# reverb.net
KiCad netlist of a schematic drawn in EAGLE
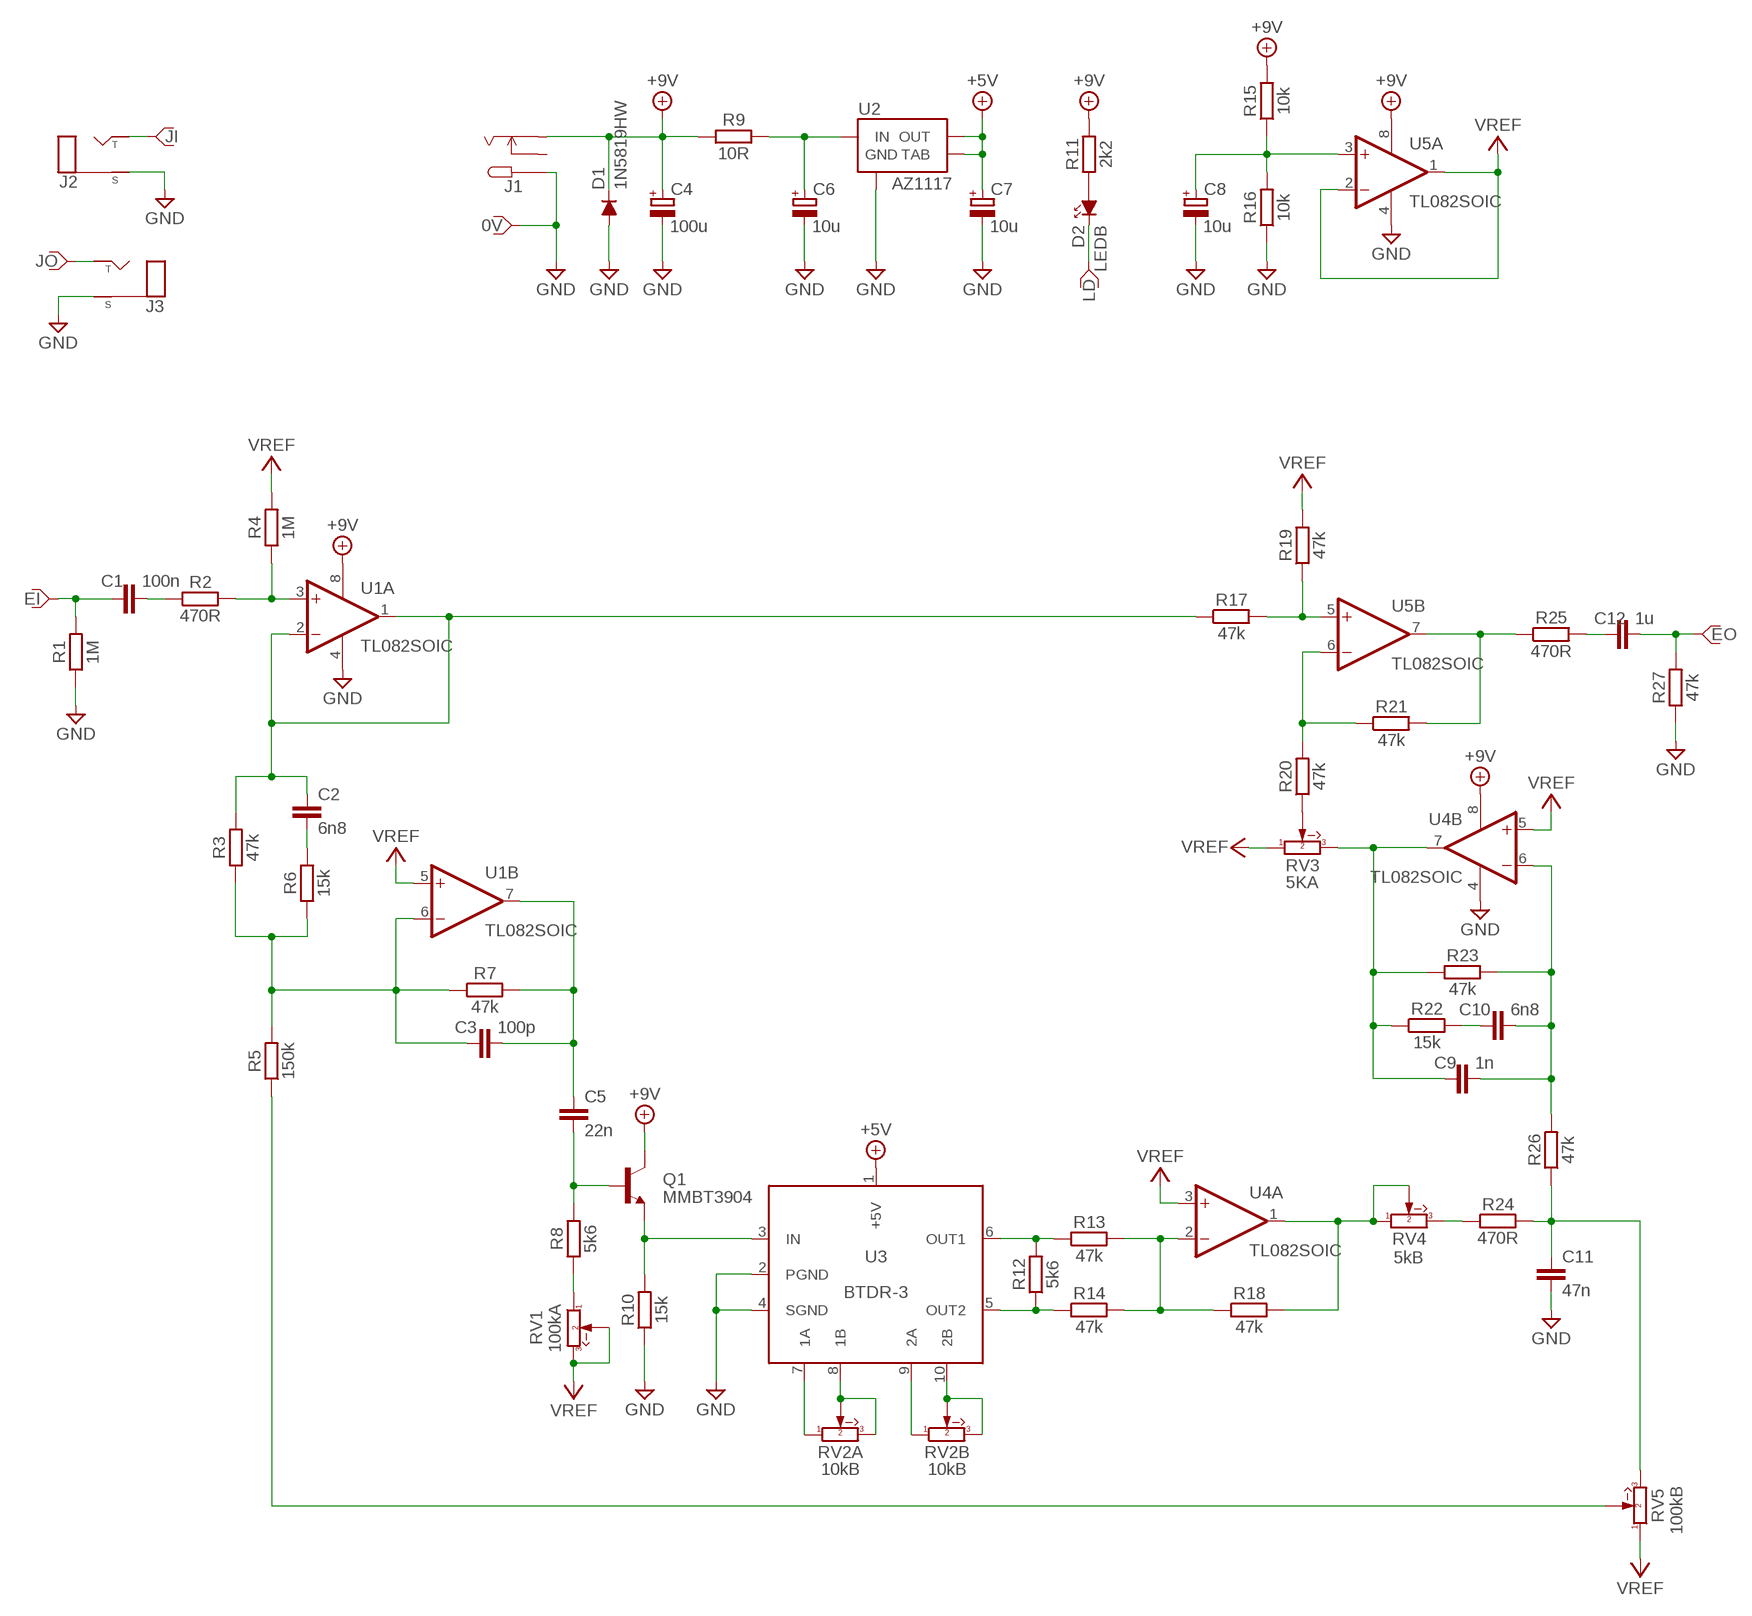
[diagram p0: schematic, sheet 1]

(export (version "E")
  (design (tool "Eeschema 10.0.6"))
  (components
    (comp (ref "C1")
      (value "100n")
      (footprint "eagle-import:C_0603")
      (libsource (lib "eagle-import") (part "CAPACITOR0603"))
    )
    (comp (ref "C2")
      (value "6n8")
      (footprint "eagle-import:C_0603")
      (libsource (lib "eagle-import") (part "CAPACITOR0603"))
    )
    (comp (ref "C3")
      (value "100p")
      (footprint "eagle-import:C_0603")
      (libsource (lib "eagle-import") (part "CAPACITOR0603"))
    )
    (comp (ref "C4")
      (value "100u")
      (footprint "eagle-import:C_E_TH_5MM")
      (libsource (lib "eagle-import") (part "CAPACITOR_POLARISEDTH_5MM"))
    )
    (comp (ref "C5")
      (value "22n")
      (footprint "eagle-import:C_0603")
      (libsource (lib "eagle-import") (part "CAPACITOR0603"))
    )
    (comp (ref "C6")
      (value "10u")
      (footprint "eagle-import:C_E_TH_5MM")
      (libsource (lib "eagle-import") (part "CAPACITOR_POLARISEDTH_5MM"))
    )
    (comp (ref "C7")
      (value "10u")
      (footprint "eagle-import:C_E_TH_5MM")
      (libsource (lib "eagle-import") (part "CAPACITOR_POLARISEDTH_5MM"))
    )
    (comp (ref "C8")
      (value "10u")
      (footprint "eagle-import:C_E_TH_5MM")
      (libsource (lib "eagle-import") (part "CAPACITOR_POLARISEDTH_5MM"))
    )
    (comp (ref "C9")
      (value "1n")
      (footprint "eagle-import:C_0603")
      (libsource (lib "eagle-import") (part "CAPACITOR0603"))
    )
    (comp (ref "C10")
      (value "6n8")
      (footprint "eagle-import:C_0603")
      (libsource (lib "eagle-import") (part "CAPACITOR0603"))
    )
    (comp (ref "C11")
      (value "47n")
      (footprint "eagle-import:C_0603")
      (libsource (lib "eagle-import") (part "CAPACITOR0603"))
    )
    (comp (ref "C12")
      (value "1u")
      (footprint "eagle-import:C_0603")
      (libsource (lib "eagle-import") (part "CAPACITOR0603"))
    )
    (comp (ref "D1")
      (value "1N5819HW")
      (footprint "eagle-import:SOD123")
      (libsource (lib "eagle-import") (part "1N5819HW"))
    )
    (comp (ref "D2")
      (value "LEDB")
      (footprint "eagle-import:LED_5MM")
      (libsource (lib "eagle-import") (part "LEDB"))
    )
    (comp (ref "J1")
      (value "DC_JACK_C2")
      (footprint "eagle-import:DC_JACK_CON_2MM")
      (libsource (lib "eagle-import") (part "DC_JACK_C2"))
    )
    (comp (ref "J2")
      (value "MONOJACK2MM")
      (footprint "eagle-import:MONOJACK_CON_2MM")
      (libsource (lib "eagle-import") (part "MONOJACK2MM"))
    )
    (comp (ref "J3")
      (value "MONOJACK2MM")
      (footprint "eagle-import:MONOJACK_CON_2MM")
      (libsource (lib "eagle-import") (part "MONOJACK2MM"))
    )
    (comp (ref "P1")
      (value "0V")
      (footprint "eagle-import:CON_PIN")
      (libsource (lib "eagle-import") (part "CON_PIN"))
    )
    (comp (ref "P2")
      (value "LD")
      (footprint "eagle-import:CON_PIN")
      (libsource (lib "eagle-import") (part "CON_PIN"))
    )
    (comp (ref "P3")
      (value "JO")
      (footprint "eagle-import:CON_PIN")
      (libsource (lib "eagle-import") (part "CON_PIN"))
    )
    (comp (ref "P4")
      (value "JI")
      (footprint "eagle-import:CON_PIN")
      (libsource (lib "eagle-import") (part "CON_PIN"))
    )
    (comp (ref "P5")
      (value "EO")
      (footprint "eagle-import:CON_PIN")
      (libsource (lib "eagle-import") (part "CON_PIN"))
    )
    (comp (ref "P6")
      (value "EI")
      (footprint "eagle-import:CON_PIN")
      (libsource (lib "eagle-import") (part "CON_PIN"))
    )
    (comp (ref "Q1")
      (value "MMBT3904")
      (footprint "eagle-import:SOT23")
      (libsource (lib "eagle-import") (part "MMBT3904"))
    )
    (comp (ref "R1")
      (value "1M")
      (footprint "eagle-import:R_0603")
      (libsource (lib "eagle-import") (part "RESISTOR0603"))
    )
    (comp (ref "R2")
      (value "470R")
      (footprint "eagle-import:R_0603")
      (libsource (lib "eagle-import") (part "RESISTOR0603"))
    )
    (comp (ref "R3")
      (value "47k")
      (footprint "eagle-import:R_0603")
      (libsource (lib "eagle-import") (part "RESISTOR0603"))
    )
    (comp (ref "R4")
      (value "1M")
      (footprint "eagle-import:R_0603")
      (libsource (lib "eagle-import") (part "RESISTOR0603"))
    )
    (comp (ref "R5")
      (value "150k")
      (footprint "eagle-import:R_0603")
      (libsource (lib "eagle-import") (part "RESISTOR0603"))
    )
    (comp (ref "R6")
      (value "15k")
      (footprint "eagle-import:R_0603")
      (libsource (lib "eagle-import") (part "RESISTOR0603"))
    )
    (comp (ref "R7")
      (value "47k")
      (footprint "eagle-import:R_0603")
      (libsource (lib "eagle-import") (part "RESISTOR0603"))
    )
    (comp (ref "R8")
      (value "5k6")
      (footprint "eagle-import:R_0603")
      (libsource (lib "eagle-import") (part "RESISTOR0603"))
    )
    (comp (ref "R9")
      (value "10R")
      (footprint "eagle-import:R_0603")
      (libsource (lib "eagle-import") (part "RESISTOR0603"))
    )
    (comp (ref "R10")
      (value "15k")
      (footprint "eagle-import:R_0603")
      (libsource (lib "eagle-import") (part "RESISTOR0603"))
    )
    (comp (ref "R11")
      (value "2k2")
      (footprint "eagle-import:R_0603")
      (libsource (lib "eagle-import") (part "RESISTOR0603"))
    )
    (comp (ref "R12")
      (value "5k6")
      (footprint "eagle-import:R_0603")
      (libsource (lib "eagle-import") (part "RESISTOR0603"))
    )
    (comp (ref "R13")
      (value "47k")
      (footprint "eagle-import:R_0603")
      (libsource (lib "eagle-import") (part "RESISTOR0603"))
    )
    (comp (ref "R14")
      (value "47k")
      (footprint "eagle-import:R_0603")
      (libsource (lib "eagle-import") (part "RESISTOR0603"))
    )
    (comp (ref "R15")
      (value "10k")
      (footprint "eagle-import:R_0603")
      (libsource (lib "eagle-import") (part "RESISTOR0603"))
    )
    (comp (ref "R16")
      (value "10k")
      (footprint "eagle-import:R_0603")
      (libsource (lib "eagle-import") (part "RESISTOR0603"))
    )
    (comp (ref "R17")
      (value "47k")
      (footprint "eagle-import:R_0603")
      (libsource (lib "eagle-import") (part "RESISTOR0603"))
    )
    (comp (ref "R18")
      (value "47k")
      (footprint "eagle-import:R_0603")
      (libsource (lib "eagle-import") (part "RESISTOR0603"))
    )
    (comp (ref "R19")
      (value "47k")
      (footprint "eagle-import:R_0603")
      (libsource (lib "eagle-import") (part "RESISTOR0603"))
    )
    (comp (ref "R20")
      (value "47k")
      (footprint "eagle-import:R_0603")
      (libsource (lib "eagle-import") (part "RESISTOR0603"))
    )
    (comp (ref "R21")
      (value "47k")
      (footprint "eagle-import:R_0603")
      (libsource (lib "eagle-import") (part "RESISTOR0603"))
    )
    (comp (ref "R22")
      (value "15k")
      (footprint "eagle-import:R_0603")
      (libsource (lib "eagle-import") (part "RESISTOR0603"))
    )
    (comp (ref "R23")
      (value "47k")
      (footprint "eagle-import:R_0603")
      (libsource (lib "eagle-import") (part "RESISTOR0603"))
    )
    (comp (ref "R24")
      (value "470R")
      (footprint "eagle-import:R_0603")
      (libsource (lib "eagle-import") (part "RESISTOR0603"))
    )
    (comp (ref "R25")
      (value "470R")
      (footprint "eagle-import:R_0603")
      (libsource (lib "eagle-import") (part "RESISTOR0603"))
    )
    (comp (ref "R26")
      (value "47k")
      (footprint "eagle-import:R_0603")
      (libsource (lib "eagle-import") (part "RESISTOR0603"))
    )
    (comp (ref "R27")
      (value "47k")
      (footprint "eagle-import:R_0603")
      (libsource (lib "eagle-import") (part "RESISTOR0603"))
    )
    (comp (ref "RV1")
      (value "100kA")
      (footprint "eagle-import:R_V_ALPHA_PCB_16MM")
      (libsource (lib "eagle-import") (part "POTENTIOMETERA"))
    )
    (comp (ref "RV2")
      (value "10kB")
      (footprint "eagle-import:R_V_ALPHA_PCB_16MM_DUAL")
      (libsource (lib "eagle-import") (part "POTENTIOMETER_DUALA"))
    )
    (comp (ref "RV3")
      (value "5KA")
      (footprint "eagle-import:R_V_ALPHA_PCB_16MM")
      (libsource (lib "eagle-import") (part "POTENTIOMETERA"))
    )
    (comp (ref "RV4")
      (value "5kB")
      (footprint "eagle-import:R_V_ALPHA_PCB_16MM")
      (libsource (lib "eagle-import") (part "POTENTIOMETERA"))
    )
    (comp (ref "RV5")
      (value "100kB")
      (footprint "eagle-import:R_V_ALPHA_PCB_16MM")
      (libsource (lib "eagle-import") (part "POTENTIOMETERA"))
    )
    (comp (ref "U1")
      (value "TL082SOIC")
      (footprint "eagle-import:SOIC8")
      (libsource (lib "eagle-import") (part "TL082SOIC"))
    )
    (comp (ref "U2")
      (value "AZ1117")
      (footprint "eagle-import:SOT223")
      (libsource (lib "eagle-import") (part "AZ1117"))
    )
    (comp (ref "U3")
      (value "BTDR-3")
      (footprint "eagle-import:BTDR-3")
      (libsource (lib "eagle-import") (part "BTDR-3"))
    )
    (comp (ref "U4")
      (value "TL082SOIC")
      (footprint "eagle-import:SOIC8")
      (libsource (lib "eagle-import") (part "TL082SOIC"))
    )
    (comp (ref "U5")
      (value "TL082SOIC")
      (footprint "eagle-import:SOIC8")
      (libsource (lib "eagle-import") (part "TL082SOIC"))
    )
  )
  (nets
    (net (code "1") (name "+5V") (class "Default")
      (node (ref "C7") (pin "+VE") (pinfunction "+_+VE") (pintype "passive"))
      (node (ref "U2") (pin "2") (pinfunction "OUT_2") (pintype "bidirectional"))
      (node (ref "U2") (pin "4") (pinfunction "TAB_4") (pintype "bidirectional"))
      (node (ref "U3") (pin "1") (pinfunction "+5V_1") (pintype "power_in"))
    )
    (net (code "2") (name "+9V") (class "Default")
      (node (ref "C4") (pin "+VE") (pinfunction "+_+VE") (pintype "passive"))
      (node (ref "D1") (pin "C") (pinfunction "C_C") (pintype "passive"))
      (node (ref "J1") (pin "S") (pinfunction "S_S") (pintype "bidirectional"))
      (node (ref "Q1") (pin "3") (pinfunction "C_3") (pintype "passive"))
      (node (ref "R11") (pin "2") (pinfunction "2_2") (pintype "passive"))
      (node (ref "R15") (pin "2") (pinfunction "2_2") (pintype "passive"))
      (node (ref "R9") (pin "2") (pinfunction "2_2") (pintype "passive"))
      (node (ref "U1") (pin "8") (pinfunction "V+_8") (pintype "power_in"))
      (node (ref "U4") (pin "8") (pinfunction "V+_8") (pintype "power_in"))
      (node (ref "U5") (pin "8") (pinfunction "V+_8") (pintype "power_in"))
    )
    (net (code "3") (name "GND") (class "Default")
      (node (ref "C11") (pin "1") (pinfunction "1_1") (pintype "passive"))
      (node (ref "C4") (pin "-VE") (pinfunction "-_-VE") (pintype "passive"))
      (node (ref "C6") (pin "-VE") (pinfunction "-_-VE") (pintype "passive"))
      (node (ref "C7") (pin "-VE") (pinfunction "-_-VE") (pintype "passive"))
      (node (ref "C8") (pin "-VE") (pinfunction "-_-VE") (pintype "passive"))
      (node (ref "D1") (pin "A") (pinfunction "A_A") (pintype "passive"))
      (node (ref "J1") (pin "T") (pinfunction "T_T") (pintype "bidirectional"))
      (node (ref "J2") (pin "S") (pinfunction "S_S") (pintype "passive"))
      (node (ref "J3") (pin "S") (pinfunction "S_S") (pintype "passive"))
      (node (ref "P1") (pin "1") (pinfunction "1_1") (pintype "bidirectional"))
      (node (ref "R1") (pin "1") (pinfunction "1_1") (pintype "passive"))
      (node (ref "R10") (pin "1") (pinfunction "1_1") (pintype "passive"))
      (node (ref "R16") (pin "1") (pinfunction "1_1") (pintype "passive"))
      (node (ref "R27") (pin "1") (pinfunction "1_1") (pintype "passive"))
      (node (ref "U1") (pin "4") (pinfunction "V-_4") (pintype "power_in"))
      (node (ref "U2") (pin "1") (pinfunction "GND_1") (pintype "power_in"))
      (node (ref "U3") (pin "2") (pinfunction "PGND_2") (pintype "power_in"))
      (node (ref "U3") (pin "4") (pinfunction "SGND_4") (pintype "power_in"))
      (node (ref "U4") (pin "4") (pinfunction "V-_4") (pintype "power_in"))
      (node (ref "U5") (pin "4") (pinfunction "V-_4") (pintype "power_in"))
    )
    (net (code "4") (name "Net-(C1-Pad1)") (class "Default")
      (node (ref "C1") (pin "1") (pinfunction "1_1") (pintype "passive"))
      (node (ref "R2") (pin "1") (pinfunction "1_1") (pintype "passive"))
    )
    (net (code "5") (name "Net-(C1-Pad2)") (class "Default")
      (node (ref "C1") (pin "2") (pinfunction "2_2") (pintype "passive"))
      (node (ref "P6") (pin "1") (pinfunction "1_1") (pintype "bidirectional"))
      (node (ref "R1") (pin "2") (pinfunction "2_2") (pintype "passive"))
    )
    (net (code "6") (name "Net-(C2-Pad1)") (class "Default")
      (node (ref "C2") (pin "1") (pinfunction "1_1") (pintype "passive"))
      (node (ref "R6") (pin "2") (pinfunction "2_2") (pintype "passive"))
    )
    (net (code "7") (name "Net-(C6-+)") (class "Default")
      (node (ref "C6") (pin "+VE") (pinfunction "+_+VE") (pintype "passive"))
      (node (ref "R9") (pin "1") (pinfunction "1_1") (pintype "passive"))
      (node (ref "U2") (pin "3") (pinfunction "IN_3") (pintype "power_in"))
    )
    (net (code "8") (name "Net-(C8-+)") (class "Default")
      (node (ref "C8") (pin "+VE") (pinfunction "+_+VE") (pintype "passive"))
      (node (ref "R15") (pin "1") (pinfunction "1_1") (pintype "passive"))
      (node (ref "R16") (pin "2") (pinfunction "2_2") (pintype "passive"))
      (node (ref "U5") (pin "3") (pinfunction "+IN_3") (pintype "input"))
    )
    (net (code "9") (name "Net-(C10-Pad2)") (class "Default")
      (node (ref "C10") (pin "2") (pinfunction "2_2") (pintype "passive"))
      (node (ref "R22") (pin "2") (pinfunction "2_2") (pintype "passive"))
    )
    (net (code "10") (name "Net-(C11-Pad2)") (class "Default")
      (node (ref "C11") (pin "2") (pinfunction "2_2") (pintype "passive"))
      (node (ref "R24") (pin "2") (pinfunction "2_2") (pintype "passive"))
      (node (ref "R26") (pin "1") (pinfunction "1_1") (pintype "passive"))
      (node (ref "RV5") (pin "3") (pinfunction "3_3") (pintype "passive"))
    )
    (net (code "11") (name "Net-(C12-Pad1)") (class "Default")
      (node (ref "C12") (pin "1") (pinfunction "1_1") (pintype "passive"))
      (node (ref "P5") (pin "1") (pinfunction "1_1") (pintype "bidirectional"))
      (node (ref "R27") (pin "2") (pinfunction "2_2") (pintype "passive"))
    )
    (net (code "12") (name "Net-(C12-Pad2)") (class "Default")
      (node (ref "C12") (pin "2") (pinfunction "2_2") (pintype "passive"))
      (node (ref "R25") (pin "2") (pinfunction "2_2") (pintype "passive"))
    )
    (net (code "13") (name "Net-(D2-PadA)") (class "Default")
      (node (ref "D2") (pin "A") (pinfunction "A_A") (pintype "passive"))
      (node (ref "R11") (pin "1") (pinfunction "1_1") (pintype "passive"))
    )
    (net (code "14") (name "Net-(D2-PadC)") (class "Default")
      (node (ref "D2") (pin "C") (pinfunction "C_C") (pintype "passive"))
      (node (ref "P2") (pin "1") (pinfunction "1_1") (pintype "bidirectional"))
    )
    (net (code "15") (name "Net-(J2-PadT)") (class "Default")
      (node (ref "J2") (pin "T") (pinfunction "T_T") (pintype "passive"))
      (node (ref "P4") (pin "1") (pinfunction "1_1") (pintype "bidirectional"))
    )
    (net (code "16") (name "Net-(J3-PadT)") (class "Default")
      (node (ref "J3") (pin "T") (pinfunction "T_T") (pintype "passive"))
      (node (ref "P3") (pin "1") (pinfunction "1_1") (pintype "bidirectional"))
    )
    (net (code "17") (name "Net-(Q1-B)") (class "Default")
      (node (ref "C5") (pin "1") (pinfunction "1_1") (pintype "passive"))
      (node (ref "Q1") (pin "1") (pinfunction "B_1") (pintype "passive"))
      (node (ref "R8") (pin "2") (pinfunction "2_2") (pintype "passive"))
    )
    (net (code "18") (name "Net-(Q1-E)") (class "Default")
      (node (ref "Q1") (pin "2") (pinfunction "E_2") (pintype "passive"))
      (node (ref "R10") (pin "2") (pinfunction "2_2") (pintype "passive"))
      (node (ref "U3") (pin "3") (pinfunction "IN_3") (pintype "input"))
    )
    (net (code "19") (name "Net-(R5-Pad1)") (class "Default")
      (node (ref "R5") (pin "1") (pinfunction "1_1") (pintype "passive"))
      (node (ref "RV5") (pin "2") (pinfunction "2_2") (pintype "passive"))
    )
    (net (code "20") (name "Net-(R8-Pad1)") (class "Default")
      (node (ref "R8") (pin "1") (pinfunction "1_1") (pintype "passive"))
      (node (ref "RV1") (pin "1") (pinfunction "1_1") (pintype "passive"))
    )
    (net (code "21") (name "Net-(R20-Pad1)") (class "Default")
      (node (ref "R20") (pin "1") (pinfunction "1_1") (pintype "passive"))
      (node (ref "RV3") (pin "2") (pinfunction "2_2") (pintype "passive"))
    )
    (net (code "22") (name "Net-(R24-Pad1)") (class "Default")
      (node (ref "R24") (pin "1") (pinfunction "1_1") (pintype "passive"))
      (node (ref "RV4") (pin "3") (pinfunction "3_3") (pintype "passive"))
    )
    (net (code "23") (name "Net-(RV2A-1)") (class "Default")
      (node (ref "RV2") (pin "A1") (pinfunction "1_A1") (pintype "passive"))
      (node (ref "U3") (pin "7") (pinfunction "1A_7") (pintype "bidirectional"))
    )
    (net (code "24") (name "Net-(RV2A-2)") (class "Default")
      (node (ref "RV2") (pin "A2") (pinfunction "2_A2") (pintype "passive"))
      (node (ref "RV2") (pin "A3") (pinfunction "3_A3") (pintype "passive"))
      (node (ref "U3") (pin "8") (pinfunction "1B_8") (pintype "bidirectional"))
    )
    (net (code "25") (name "Net-(RV2B-1)") (class "Default")
      (node (ref "RV2") (pin "B1") (pinfunction "1_B1") (pintype "passive"))
      (node (ref "U3") (pin "9") (pinfunction "2A_9") (pintype "bidirectional"))
    )
    (net (code "26") (name "Net-(RV2B-2)") (class "Default")
      (node (ref "RV2") (pin "B2") (pinfunction "2_B2") (pintype "passive"))
      (node (ref "RV2") (pin "B3") (pinfunction "3_B3") (pintype "passive"))
      (node (ref "U3") (pin "10") (pinfunction "2B_10") (pintype "bidirectional"))
    )
    (net (code "27") (name "Net-(U1A-+IN)") (class "Default")
      (node (ref "R2") (pin "2") (pinfunction "2_2") (pintype "passive"))
      (node (ref "R4") (pin "1") (pinfunction "1_1") (pintype "passive"))
      (node (ref "U1") (pin "3") (pinfunction "+IN_3") (pintype "input"))
    )
    (net (code "28") (name "Net-(U1A--IN)") (class "Default")
      (node (ref "C2") (pin "2") (pinfunction "2_2") (pintype "passive"))
      (node (ref "R17") (pin "1") (pinfunction "1_1") (pintype "passive"))
      (node (ref "R3") (pin "2") (pinfunction "2_2") (pintype "passive"))
      (node (ref "U1") (pin "1") (pinfunction "OUT_1") (pintype "output"))
      (node (ref "U1") (pin "2") (pinfunction "-IN_2") (pintype "input"))
    )
    (net (code "29") (name "Net-(U1B--IN)") (class "Default")
      (node (ref "C3") (pin "2") (pinfunction "2_2") (pintype "passive"))
      (node (ref "R3") (pin "1") (pinfunction "1_1") (pintype "passive"))
      (node (ref "R5") (pin "2") (pinfunction "2_2") (pintype "passive"))
      (node (ref "R6") (pin "1") (pinfunction "1_1") (pintype "passive"))
      (node (ref "R7") (pin "1") (pinfunction "1_1") (pintype "passive"))
      (node (ref "U1") (pin "6") (pinfunction "-IN_6") (pintype "input"))
    )
    (net (code "30") (name "Net-(U1B-OUT)") (class "Default")
      (node (ref "C3") (pin "1") (pinfunction "1_1") (pintype "passive"))
      (node (ref "C5") (pin "2") (pinfunction "2_2") (pintype "passive"))
      (node (ref "R7") (pin "2") (pinfunction "2_2") (pintype "passive"))
      (node (ref "U1") (pin "7") (pinfunction "OUT_7") (pintype "output"))
    )
    (net (code "31") (name "Net-(U3-OUT1)") (class "Default")
      (node (ref "R12") (pin "2") (pinfunction "2_2") (pintype "passive"))
      (node (ref "R13") (pin "1") (pinfunction "1_1") (pintype "passive"))
      (node (ref "U3") (pin "6") (pinfunction "OUT1_6") (pintype "output"))
    )
    (net (code "32") (name "Net-(U3-OUT2)") (class "Default")
      (node (ref "R12") (pin "1") (pinfunction "1_1") (pintype "passive"))
      (node (ref "R14") (pin "1") (pinfunction "1_1") (pintype "passive"))
      (node (ref "U3") (pin "5") (pinfunction "OUT2_5") (pintype "output"))
    )
    (net (code "33") (name "Net-(U4A--IN)") (class "Default")
      (node (ref "R13") (pin "2") (pinfunction "2_2") (pintype "passive"))
      (node (ref "R14") (pin "2") (pinfunction "2_2") (pintype "passive"))
      (node (ref "R18") (pin "1") (pinfunction "1_1") (pintype "passive"))
      (node (ref "U4") (pin "2") (pinfunction "-IN_2") (pintype "input"))
    )
    (net (code "34") (name "Net-(U4A-OUT)") (class "Default")
      (node (ref "R18") (pin "2") (pinfunction "2_2") (pintype "passive"))
      (node (ref "RV4") (pin "1") (pinfunction "1_1") (pintype "passive"))
      (node (ref "RV4") (pin "2") (pinfunction "2_2") (pintype "passive"))
      (node (ref "U4") (pin "1") (pinfunction "OUT_1") (pintype "output"))
    )
    (net (code "35") (name "Net-(U4B--IN)") (class "Default")
      (node (ref "C10") (pin "1") (pinfunction "1_1") (pintype "passive"))
      (node (ref "C9") (pin "1") (pinfunction "1_1") (pintype "passive"))
      (node (ref "R23") (pin "2") (pinfunction "2_2") (pintype "passive"))
      (node (ref "R26") (pin "2") (pinfunction "2_2") (pintype "passive"))
      (node (ref "U4") (pin "6") (pinfunction "-IN_6") (pintype "input"))
    )
    (net (code "36") (name "Net-(U4B-OUT)") (class "Default")
      (node (ref "C9") (pin "2") (pinfunction "2_2") (pintype "passive"))
      (node (ref "R22") (pin "1") (pinfunction "1_1") (pintype "passive"))
      (node (ref "R23") (pin "1") (pinfunction "1_1") (pintype "passive"))
      (node (ref "RV3") (pin "3") (pinfunction "3_3") (pintype "passive"))
      (node (ref "U4") (pin "7") (pinfunction "OUT_7") (pintype "output"))
    )
    (net (code "37") (name "Net-(U5B-+IN)") (class "Default")
      (node (ref "R17") (pin "2") (pinfunction "2_2") (pintype "passive"))
      (node (ref "R19") (pin "1") (pinfunction "1_1") (pintype "passive"))
      (node (ref "U5") (pin "5") (pinfunction "+IN_5") (pintype "input"))
    )
    (net (code "38") (name "Net-(U5B--IN)") (class "Default")
      (node (ref "R20") (pin "2") (pinfunction "2_2") (pintype "passive"))
      (node (ref "R21") (pin "1") (pinfunction "1_1") (pintype "passive"))
      (node (ref "U5") (pin "6") (pinfunction "-IN_6") (pintype "input"))
    )
    (net (code "39") (name "Net-(U5B-OUT)") (class "Default")
      (node (ref "R21") (pin "2") (pinfunction "2_2") (pintype "passive"))
      (node (ref "R25") (pin "1") (pinfunction "1_1") (pintype "passive"))
      (node (ref "U5") (pin "7") (pinfunction "OUT_7") (pintype "output"))
    )
    (net (code "40") (name "VREF") (class "Default")
      (node (ref "R19") (pin "2") (pinfunction "2_2") (pintype "passive"))
      (node (ref "R4") (pin "2") (pinfunction "2_2") (pintype "passive"))
      (node (ref "RV1") (pin "2") (pinfunction "2_2") (pintype "passive"))
      (node (ref "RV1") (pin "3") (pinfunction "3_3") (pintype "passive"))
      (node (ref "RV3") (pin "1") (pinfunction "1_1") (pintype "passive"))
      (node (ref "RV5") (pin "1") (pinfunction "1_1") (pintype "passive"))
      (node (ref "U1") (pin "5") (pinfunction "+IN_5") (pintype "input"))
      (node (ref "U4") (pin "3") (pinfunction "+IN_3") (pintype "input"))
      (node (ref "U4") (pin "5") (pinfunction "+IN_5") (pintype "input"))
      (node (ref "U5") (pin "1") (pinfunction "OUT_1") (pintype "output"))
      (node (ref "U5") (pin "2") (pinfunction "-IN_2") (pintype "input"))
    )
    (net (code "41") (name "unconnected-(J1-PadSW)") (class "Default")
      (node (ref "J1") (pin "SW") (pinfunction "SW_SW") (pintype "bidirectional"))
    )
  )
)
